# Mcu.net
KiCad netlist of a schematic drawn in Altium Designer
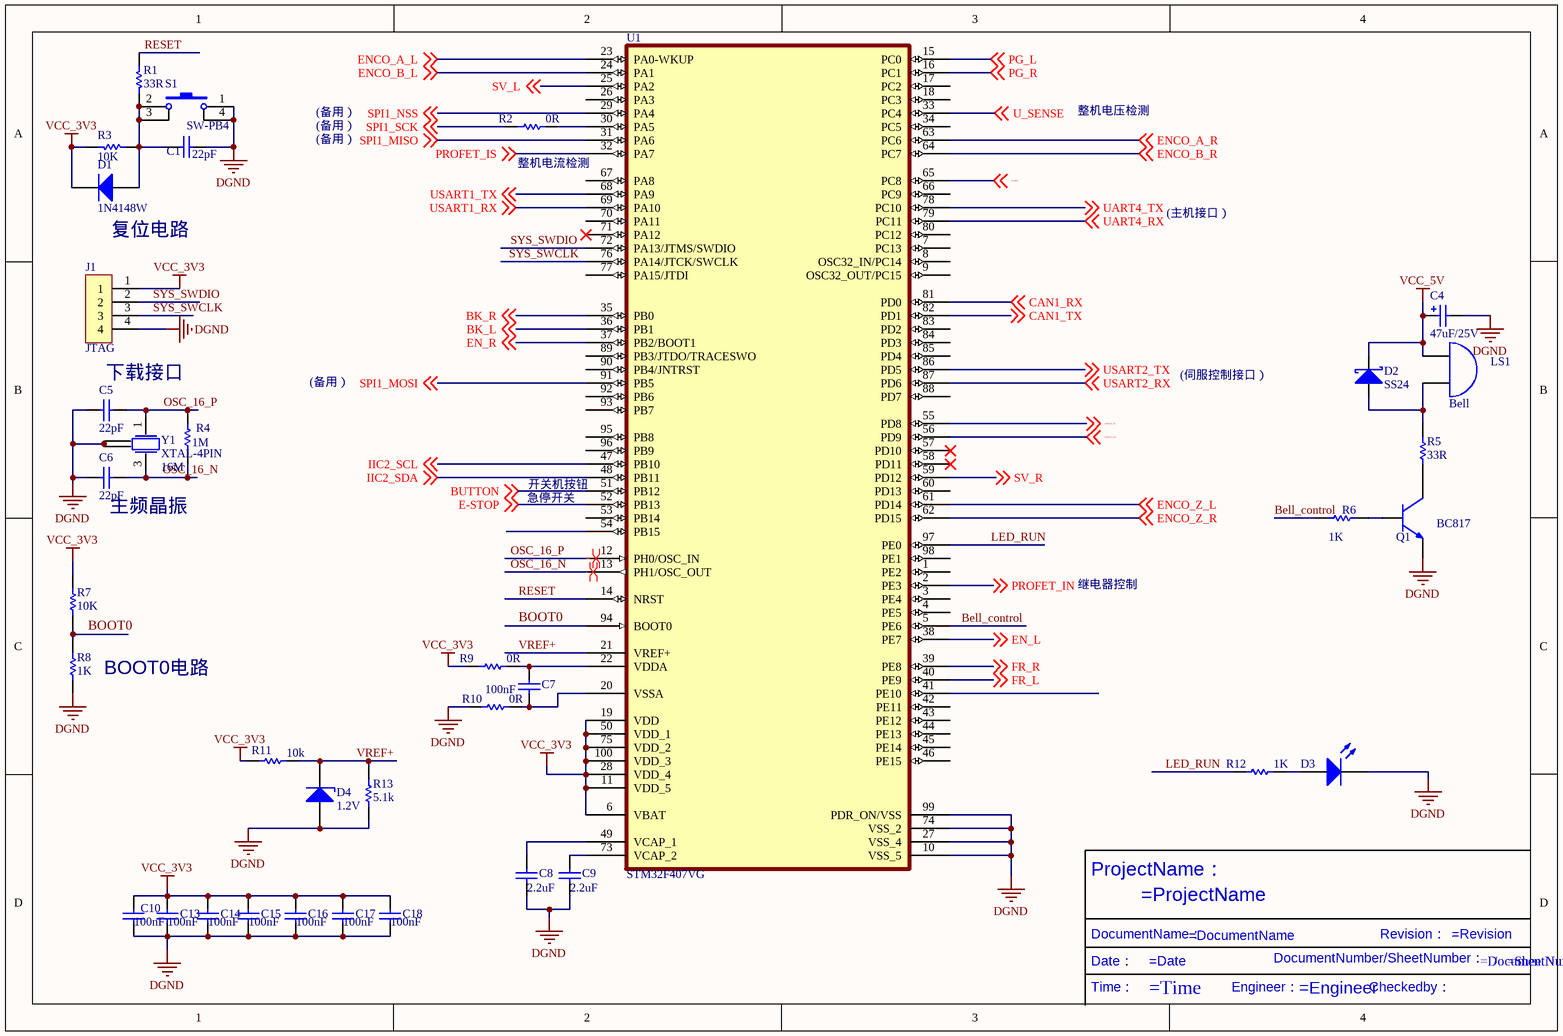
[diagram p0: Mcu.SchDoc]

(export (version "E")
  (design (tool "Eeschema 10.0.6"))
  (components
    (comp (ref "C1")
      (value "22pF")
      (footprint "C0805")
      (description "Capacitor")
      (fields (field (name "Comment") "Cap") (field (name "PUBLISHER") "Altium Limited"))
      (libsource (lib "boocax_schlib") (part "Cap"))
    )
    (comp (ref "C4")
      (value "47uF/25V")
      (footprint "CAP-1206")
      (description "Polarized Capacitor (Radial)")
      (fields (field (name "Comment") "Cap Pol1") (field (name "PUBLISHER") "Altium Limited"))
      (libsource (lib "boocax_schlib") (part "Cap Pol1"))
    )
    (comp (ref "C5")
      (value "22pF")
      (footprint "C0805")
      (description "Capacitor")
      (fields (field (name "Comment") "Cap") (field (name "PUBLISHER") "Altium Limited"))
      (libsource (lib "boocax_schlib") (part "Cap"))
    )
    (comp (ref "C6")
      (value "22pF")
      (footprint "C0805")
      (description "Capacitor")
      (fields (field (name "Comment") "Cap") (field (name "PUBLISHER") "Altium Limited"))
      (libsource (lib "boocax_schlib") (part "Cap"))
    )
    (comp (ref "C7")
      (value "100nF")
      (footprint "C0805")
      (description "Capacitor")
      (fields (field (name "Comment") "Cap") (field (name "PUBLISHER") "Altium Limited"))
      (libsource (lib "boocax_schlib") (part "Cap"))
    )
    (comp (ref "C8")
      (value "2.2uF")
      (footprint "C0805")
      (description "Capacitor")
      (fields (field (name "Comment") "Cap") (field (name "PUBLISHER") "Altium Limited"))
      (libsource (lib "boocax_schlib") (part "Cap"))
    )
    (comp (ref "C9")
      (value "2.2uF")
      (footprint "C0805")
      (description "Capacitor")
      (fields (field (name "Comment") "Cap") (field (name "PUBLISHER") "Altium Limited"))
      (libsource (lib "boocax_schlib") (part "Cap"))
    )
    (comp (ref "C10")
      (value "100nF")
      (footprint "C0805")
      (description "Capacitor")
      (fields (field (name "Comment") "Cap") (field (name "PUBLISHER") "Altium Limited"))
      (libsource (lib "boocax_schlib") (part "Cap"))
    )
    (comp (ref "C13")
      (value "100nF")
      (footprint "C0805")
      (description "Capacitor")
      (fields (field (name "Comment") "Cap") (field (name "PUBLISHER") "Altium Limited"))
      (libsource (lib "boocax_schlib") (part "Cap"))
    )
    (comp (ref "C14")
      (value "100nF")
      (footprint "C0805")
      (description "Capacitor")
      (fields (field (name "Comment") "Cap") (field (name "PUBLISHER") "Altium Limited"))
      (libsource (lib "boocax_schlib") (part "Cap"))
    )
    (comp (ref "C15")
      (value "100nF")
      (footprint "C0805")
      (description "Capacitor")
      (fields (field (name "Comment") "Cap") (field (name "PUBLISHER") "Altium Limited"))
      (libsource (lib "boocax_schlib") (part "Cap"))
    )
    (comp (ref "C16")
      (value "100nF")
      (footprint "C0805")
      (description "Capacitor")
      (fields (field (name "Comment") "Cap") (field (name "PUBLISHER") "Altium Limited"))
      (libsource (lib "boocax_schlib") (part "Cap"))
    )
    (comp (ref "C17")
      (value "100nF")
      (footprint "C0805")
      (description "Capacitor")
      (fields (field (name "Comment") "Cap") (field (name "PUBLISHER") "Altium Limited"))
      (libsource (lib "boocax_schlib") (part "Cap"))
    )
    (comp (ref "C18")
      (value "100nF")
      (footprint "C0805")
      (description "Capacitor")
      (fields (field (name "Comment") "Cap") (field (name "PUBLISHER") "Altium Limited"))
      (libsource (lib "boocax_schlib") (part "Cap"))
    )
    (comp (ref "D1")
      (value "1N4148W")
      (footprint "DIODE-1206")
      (description "二极管")
      (fields (field (name "Comment") "Diode") (field (name "PUBLISHER") "Altium Limited"))
      (libsource (lib "founder") (part "Diode"))
    )
    (comp (ref "D2")
      (value "SS24")
      (footprint "DIODE-SMA")
      (description "肖特基二极管")
      (fields (field (name "Comment") "Diode-Schottky") (field (name "PUBLISHER") "Altium Limited"))
      (libsource (lib "boocax_schlib-20171017-1-dkw") (part "Diode-Schottky"))
    )
    (comp (ref "D3")
      (value "LED0")
      (footprint "LED_0805")
      (description "发光二极管")
      (fields (field (name "PUBLISHER") "Altium Limited"))
      (libsource (lib "founder") (part "LED0"))
    )
    (comp (ref "D4")
      (value "1.2V")
      (footprint "DIODE-1206")
      (description "稳压二极管")
      (fields (field (name "Comment") "Diode-Z") (field (name "PUBLISHER") "Altium Limited"))
      (libsource (lib "Fszhang") (part "Diode-Z"))
    )
    (comp (ref "J1")
      (value "JTAG")
      (footprint "PORT-SIP4-2.54")
      (libsource (lib "boocax_schlib") (part "Conn_1*4_1"))
    )
    (comp (ref "LS1")
      (value "Bell")
      (footprint "PIN2")
      (description "Electrical Bell")
      (fields (field (name "PUBLISHER") "Altium Limited"))
      (libsource (lib "Miscellaneous Devices") (part "Bell"))
    )
    (comp (ref "Q1")
      (value "BC817")
      (footprint "SOT-23_N")
      (description "NPN 45V 功耗 310mW")
      (libsource (lib "Schlib1") (part "mNPN"))
    )
    (comp (ref "R1")
      (value "33R")
      (footprint "R0805")
      (description "Resistor")
      (fields (field (name "Comment") "Res1") (field (name "PUBLISHER") "Altium Limited"))
      (libsource (lib "boocax_schlib") (part "Res1"))
    )
    (comp (ref "R2")
      (value "0R")
      (footprint "R0805")
      (description "Resistor")
      (fields (field (name "Comment") "Res1") (field (name "PUBLISHER") "Altium Limited"))
      (libsource (lib "boocax_schlib") (part "Res1"))
    )
    (comp (ref "R3")
      (value "10K")
      (footprint "R0805")
      (description "Resistor")
      (fields (field (name "Comment") "Res1") (field (name "PUBLISHER") "Altium Limited"))
      (libsource (lib "boocax_schlib") (part "Res1"))
    )
    (comp (ref "R4")
      (value "1M")
      (footprint "R0805")
      (description "Resistor")
      (fields (field (name "Comment") "Res1") (field (name "PUBLISHER") "Altium Limited"))
      (libsource (lib "boocax_schlib") (part "Res1"))
    )
    (comp (ref "R5")
      (value "33R")
      (footprint "R0805")
      (description "Resistor")
      (fields (field (name "Comment") "Res1") (field (name "PUBLISHER") "Altium Limited"))
      (libsource (lib "boocax_schlib") (part "Res1"))
    )
    (comp (ref "R6")
      (value "1K")
      (footprint "R0805")
      (description "Resistor")
      (fields (field (name "Comment") "Res1") (field (name "PUBLISHER") "Altium Limited"))
      (libsource (lib "boocax_schlib") (part "Res1"))
    )
    (comp (ref "R7")
      (value "10K")
      (footprint "R0805")
      (description "Resistor")
      (fields (field (name "Comment") "Res1") (field (name "PUBLISHER") "Altium Limited"))
      (libsource (lib "boocax_schlib") (part "Res1"))
    )
    (comp (ref "R8")
      (value "1K")
      (footprint "R0805")
      (description "Resistor")
      (fields (field (name "Comment") "Res1") (field (name "PUBLISHER") "Altium Limited"))
      (libsource (lib "boocax_schlib") (part "Res1"))
    )
    (comp (ref "R9")
      (value "0R")
      (footprint "R0805")
      (description "Resistor")
      (fields (field (name "Comment") "Res1") (field (name "PUBLISHER") "Altium Limited"))
      (libsource (lib "boocax_schlib") (part "Res1"))
    )
    (comp (ref "R10")
      (value "0R")
      (footprint "R0805")
      (description "Resistor")
      (fields (field (name "Comment") "Res1") (field (name "PUBLISHER") "Altium Limited"))
      (libsource (lib "boocax_schlib") (part "Res1"))
    )
    (comp (ref "R11")
      (value "10k")
      (footprint "R0805")
      (description "Resistor")
      (fields (field (name "Comment") "Res1") (field (name "PUBLISHER") "Altium Limited"))
      (libsource (lib "boocax_schlib") (part "Res1"))
    )
    (comp (ref "R12")
      (value "1K")
      (footprint "R0805")
      (description "Resistor")
      (fields (field (name "Comment") "Res1") (field (name "PUBLISHER") "Altium Limited"))
      (libsource (lib "boocax_schlib") (part "Res1"))
    )
    (comp (ref "R13")
      (value "5.1k")
      (footprint "R0805")
      (description "Resistor")
      (fields (field (name "Comment") "Res1") (field (name "PUBLISHER") "Altium Limited"))
      (libsource (lib "boocax_schlib") (part "Res1"))
    )
    (comp (ref "S1")
      (value "SW-PB4")
      (footprint "RESET-SMD-1O4")
      (description "微动开关")
      (fields (field (name "PUBLISHER") "Altium Limited"))
      (libsource (lib "boocax_schlib") (part "SW-PB4"))
    )
    (comp (ref "U1")
      (value "STM32F407VG")
      (footprint "100T1_N")
      (libsource (lib "boocax_schlib") (part "STM32F407VG"))
    )
    (comp (ref "Y1")
      (value "XTAL-4PIN")
      (footprint "EPSON-16M")
      (fields (field (name "ALTIUM_VALUE") "16M"))
      (libsource (lib "fszhang") (part "XTAL-4PIN"))
    )
  )
  (nets
    (net (code "9") (name "/BOOT0") (class "Default")
      (node (ref "R7") (pin "2") (pinfunction "2_2") (pintype "passive"))
      (node (ref "R8") (pin "2") (pinfunction "2_2") (pintype "passive"))
      (node (ref "U1") (pin "94") (pinfunction "BOOT0_94") (pintype "input"))
    )
    (net (code "10") (name "/Bell_control") (class "Default")
      (node (ref "R6") (pin "2") (pinfunction "2_2") (pintype "passive"))
      (node (ref "U1") (pin "5") (pinfunction "PE6_5") (pintype "bidirectional"))
    )
    (net (code "16") (name "/LED_RUN") (class "Default")
      (node (ref "R12") (pin "2") (pinfunction "2_2") (pintype "passive"))
      (node (ref "U1") (pin "97") (pinfunction "PE0_97") (pintype "bidirectional"))
    )
    (net (code "17") (name "/OSC_16_N") (class "Default")
      (node (ref "C6") (pin "1") (pinfunction "1_1") (pintype "passive"))
      (node (ref "R4") (pin "1") (pinfunction "1_1") (pintype "passive"))
      (node (ref "U1") (pin "13") (pinfunction "PH1/OSC_OUT_13") (pintype "output"))
      (node (ref "Y1") (pin "3") (pinfunction "3_3") (pintype "passive"))
    )
    (net (code "18") (name "/OSC_16_P") (class "Default")
      (node (ref "C5") (pin "2") (pinfunction "2_2") (pintype "passive"))
      (node (ref "R4") (pin "2") (pinfunction "2_2") (pintype "passive"))
      (node (ref "U1") (pin "12") (pinfunction "PH0/OSC_IN_12") (pintype "input"))
      (node (ref "Y1") (pin "1") (pinfunction "1_1") (pintype "passive"))
    )
    (net (code "20") (name "/RESET") (class "Default")
      (node (ref "R1") (pin "1") (pinfunction "1_1") (pintype "passive"))
      (node (ref "U1") (pin "14") (pinfunction "NRST_14") (pintype "bidirectional"))
    )
    (net (code "22") (name "/SYS_SWCLK") (class "Default")
      (node (ref "J1") (pin "3") (pinfunction "3_3") (pintype "passive"))
      (node (ref "U1") (pin "76") (pinfunction "PA14/JTCK/SWCLK_76") (pintype "bidirectional"))
    )
    (net (code "23") (name "/SYS_SWDIO") (class "Default")
      (node (ref "J1") (pin "2") (pinfunction "2_2") (pintype "passive"))
      (node (ref "U1") (pin "72") (pinfunction "PA13/JTMS/SWDIO_72") (pintype "bidirectional"))
    )
    (net (code "25") (name "/VREF+") (class "Default")
      (node (ref "D4") (pin "2") (pinfunction "K_2") (pintype "passive"))
      (node (ref "R11") (pin "1") (pinfunction "1_1") (pintype "passive"))
      (node (ref "R13") (pin "2") (pinfunction "2_2") (pintype "passive"))
      (node (ref "U1") (pin "21") (pinfunction "VREF+_21") (pintype "power_in"))
    )
    (net (code "27") (name "B-STOP") (class "Default")
      (node (ref "U1") (pin "65") (pinfunction "PC8_65") (pintype "bidirectional"))
    )
    (net (code "28") (name "BK_L") (class "Default")
      (node (ref "U1") (pin "36") (pinfunction "PB1_36") (pintype "bidirectional"))
    )
    (net (code "29") (name "BK_R") (class "Default")
      (node (ref "U1") (pin "35") (pinfunction "PB0_35") (pintype "bidirectional"))
    )
    (net (code "30") (name "BUTTON") (class "Default")
      (node (ref "U1") (pin "51") (pinfunction "PB12_51") (pintype "bidirectional"))
    )
    (net (code "31") (name "CAN1_RX") (class "Default")
      (node (ref "U1") (pin "81") (pinfunction "PD0_81") (pintype "bidirectional"))
    )
    (net (code "32") (name "CAN1_TX") (class "Default")
      (node (ref "U1") (pin "82") (pinfunction "PD1_82") (pintype "bidirectional"))
    )
    (net (code "33") (name "DGND") (class "Default")
      (node (ref "C1") (pin "1") (pinfunction "1_1") (pintype "passive"))
      (node (ref "C10") (pin "2") (pinfunction "2_2") (pintype "passive"))
      (node (ref "C13") (pin "2") (pinfunction "2_2") (pintype "passive"))
      (node (ref "C14") (pin "2") (pinfunction "2_2") (pintype "passive"))
      (node (ref "C15") (pin "2") (pinfunction "2_2") (pintype "passive"))
      (node (ref "C16") (pin "2") (pinfunction "2_2") (pintype "passive"))
      (node (ref "C17") (pin "2") (pinfunction "2_2") (pintype "passive"))
      (node (ref "C18") (pin "2") (pinfunction "2_2") (pintype "passive"))
      (node (ref "C4") (pin "2") (pinfunction "2_2") (pintype "passive"))
      (node (ref "C5") (pin "1") (pinfunction "1_1") (pintype "passive"))
      (node (ref "C6") (pin "2") (pinfunction "2_2") (pintype "passive"))
      (node (ref "C8") (pin "2") (pinfunction "2_2") (pintype "passive"))
      (node (ref "C9") (pin "2") (pinfunction "2_2") (pintype "passive"))
      (node (ref "D3") (pin "2") (pinfunction "K_2") (pintype "passive"))
      (node (ref "D4") (pin "1") (pinfunction "A_1") (pintype "passive"))
      (node (ref "J1") (pin "4") (pinfunction "4_4") (pintype "passive"))
      (node (ref "Q1") (pin "2") (pinfunction "E_2") (pintype "passive"))
      (node (ref "R10") (pin "2") (pinfunction "2_2") (pintype "passive"))
      (node (ref "R13") (pin "1") (pinfunction "1_1") (pintype "passive"))
      (node (ref "R8") (pin "1") (pinfunction "1_1") (pintype "passive"))
      (node (ref "S1") (pin "1") (pinfunction "1_1") (pintype "passive"))
      (node (ref "S1") (pin "4") (pinfunction "4_4") (pintype "passive"))
      (node (ref "U1") (pin "10") (pinfunction "VSS_5_10") (pintype "passive"))
      (node (ref "U1") (pin "27") (pinfunction "VSS_4_27") (pintype "passive"))
      (node (ref "U1") (pin "74") (pinfunction "VSS_2_74") (pintype "passive"))
      (node (ref "U1") (pin "99") (pinfunction "PDR_ON/VSS_99") (pintype "power_in"))
      (node (ref "Y1") (pin "2") (pinfunction "2_2") (pintype "passive"))
      (node (ref "Y1") (pin "4") (pinfunction "4_4") (pintype "passive"))
    )
    (net (code "34") (name "E-STOP") (class "Default")
      (node (ref "U1") (pin "52") (pinfunction "PB13_52") (pintype "bidirectional"))
    )
    (net (code "35") (name "ENCO_A_L") (class "Default")
      (node (ref "U1") (pin "23") (pinfunction "PA0-WKUP_23") (pintype "bidirectional"))
    )
    (net (code "36") (name "ENCO_A_R") (class "Default")
      (node (ref "U1") (pin "63") (pinfunction "PC6_63") (pintype "bidirectional"))
    )
    (net (code "37") (name "ENCO_B_L") (class "Default")
      (node (ref "U1") (pin "24") (pinfunction "PA1_24") (pintype "bidirectional"))
    )
    (net (code "38") (name "ENCO_B_R") (class "Default")
      (node (ref "U1") (pin "64") (pinfunction "PC7_64") (pintype "bidirectional"))
    )
    (net (code "39") (name "ENCO_Z_L") (class "Default")
      (node (ref "U1") (pin "61") (pinfunction "PD14_61") (pintype "bidirectional"))
    )
    (net (code "40") (name "ENCO_Z_R") (class "Default")
      (node (ref "U1") (pin "62") (pinfunction "PD15_62") (pintype "bidirectional"))
    )
    (net (code "41") (name "EN_L") (class "Default")
      (node (ref "U1") (pin "38") (pinfunction "PE7_38") (pintype "bidirectional"))
    )
    (net (code "42") (name "EN_R") (class "Default")
      (node (ref "U1") (pin "37") (pinfunction "PB2/BOOT1_37") (pintype "bidirectional"))
    )
    (net (code "43") (name "FR_L") (class "Default")
      (node (ref "U1") (pin "40") (pinfunction "PE9_40") (pintype "bidirectional"))
    )
    (net (code "44") (name "FR_R") (class "Default")
      (node (ref "U1") (pin "39") (pinfunction "PE8_39") (pintype "bidirectional"))
    )
    (net (code "45") (name "IIC2_SCL") (class "Default")
      (node (ref "U1") (pin "47") (pinfunction "PB10_47") (pintype "bidirectional"))
    )
    (net (code "46") (name "IIC2_SDA") (class "Default")
      (node (ref "U1") (pin "48") (pinfunction "PB11_48") (pintype "bidirectional"))
    )
    (net (code "47") (name "Net-(D1-A)") (class "Default")
      (node (ref "C1") (pin "2") (pinfunction "2_2") (pintype "passive"))
      (node (ref "D1") (pin "1") (pinfunction "A_1") (pintype "passive"))
      (node (ref "R1") (pin "2") (pinfunction "2_2") (pintype "passive"))
      (node (ref "R3") (pin "1") (pinfunction "1_1") (pintype "passive"))
      (node (ref "S1") (pin "2") (pinfunction "2_2") (pintype "passive"))
      (node (ref "S1") (pin "3") (pinfunction "3_3") (pintype "passive"))
    )
    (net (code "48") (name "Net-(D2-A)") (class "Default")
      (node (ref "D2") (pin "1") (pinfunction "A_1") (pintype "passive"))
      (node (ref "LS1") (pin "2") (pinfunction "B_2") (pintype "passive"))
      (node (ref "R5") (pin "1") (pinfunction "1_1") (pintype "passive"))
    )
    (net (code "49") (name "Net-(D3-A)") (class "Default")
      (node (ref "D3") (pin "1") (pinfunction "A_1") (pintype "passive"))
      (node (ref "R12") (pin "1") (pinfunction "1_1") (pintype "passive"))
    )
    (net (code "50") (name "Net-(Q1-B)") (class "Default")
      (node (ref "Q1") (pin "1") (pinfunction "B_1") (pintype "passive"))
      (node (ref "R6") (pin "1") (pinfunction "1_1") (pintype "passive"))
    )
    (net (code "51") (name "Net-(Q1-C)") (class "Default")
      (node (ref "Q1") (pin "3") (pinfunction "C_3") (pintype "passive"))
      (node (ref "R5") (pin "2") (pinfunction "2_2") (pintype "passive"))
    )
    (net (code "52") (name "Net-(U1-PA5)") (class "Default")
      (node (ref "R2") (pin "1") (pinfunction "1_1") (pintype "passive"))
      (node (ref "U1") (pin "30") (pinfunction "PA5_30") (pintype "bidirectional"))
    )
    (net (code "53") (name "Net-(U1-VCAP_1)") (class "Default")
      (node (ref "C8") (pin "1") (pinfunction "1_1") (pintype "passive"))
      (node (ref "U1") (pin "49") (pinfunction "VCAP_1_49") (pintype "power_in"))
    )
    (net (code "54") (name "Net-(U1-VCAP_2)") (class "Default")
      (node (ref "C9") (pin "1") (pinfunction "1_1") (pintype "passive"))
      (node (ref "U1") (pin "73") (pinfunction "VCAP_2_73") (pintype "power_in"))
    )
    (net (code "55") (name "Net-(U1-VDDA)") (class "Default")
      (node (ref "C7") (pin "2") (pinfunction "2_2") (pintype "passive"))
      (node (ref "R9") (pin "1") (pinfunction "1_1") (pintype "passive"))
      (node (ref "U1") (pin "22") (pinfunction "VDDA_22") (pintype "power_in"))
    )
    (net (code "56") (name "Net-(U1-VSSA)") (class "Default")
      (node (ref "C7") (pin "1") (pinfunction "1_1") (pintype "passive"))
      (node (ref "R10") (pin "1") (pinfunction "1_1") (pintype "passive"))
      (node (ref "U1") (pin "20") (pinfunction "VSSA_20") (pintype "power_in"))
    )
    (net (code "57") (name "PG_L") (class "Default")
      (node (ref "U1") (pin "15") (pinfunction "PC0_15") (pintype "bidirectional"))
    )
    (net (code "58") (name "PG_R") (class "Default")
      (node (ref "U1") (pin "16") (pinfunction "PC1_16") (pintype "bidirectional"))
    )
    (net (code "59") (name "PROFET_IN") (class "Default")
      (node (ref "U1") (pin "2") (pinfunction "PE3_2") (pintype "bidirectional"))
    )
    (net (code "60") (name "PROFET_IS") (class "Default")
      (node (ref "U1") (pin "32") (pinfunction "PA7_32") (pintype "bidirectional"))
    )
    (net (code "61") (name "SPI1_MISO") (class "Default")
      (node (ref "U1") (pin "31") (pinfunction "PA6_31") (pintype "bidirectional"))
    )
    (net (code "62") (name "SPI1_MOSI") (class "Default")
      (node (ref "U1") (pin "91") (pinfunction "PB5_91") (pintype "bidirectional"))
    )
    (net (code "63") (name "SPI1_NSS") (class "Default")
      (node (ref "U1") (pin "29") (pinfunction "PA4_29") (pintype "bidirectional"))
    )
    (net (code "64") (name "SPI1_SCK") (class "Default")
      (node (ref "R2") (pin "2") (pinfunction "2_2") (pintype "passive"))
    )
    (net (code "65") (name "SV_L") (class "Default")
      (node (ref "U1") (pin "25") (pinfunction "PA2_25") (pintype "bidirectional"))
    )
    (net (code "66") (name "SV_R") (class "Default")
      (node (ref "U1") (pin "59") (pinfunction "PD12_59") (pintype "bidirectional"))
    )
    (net (code "67") (name "UART4_RX") (class "Default")
      (node (ref "U1") (pin "79") (pinfunction "PC11_79") (pintype "bidirectional"))
    )
    (net (code "68") (name "UART4_TX") (class "Default")
      (node (ref "U1") (pin "78") (pinfunction "PC10_78") (pintype "bidirectional"))
    )
    (net (code "69") (name "USART1_RX") (class "Default")
      (node (ref "U1") (pin "69") (pinfunction "PA10_69") (pintype "bidirectional"))
    )
    (net (code "70") (name "USART1_TX") (class "Default")
      (node (ref "U1") (pin "68") (pinfunction "PA9_68") (pintype "bidirectional"))
    )
    (net (code "71") (name "USART2_RX") (class "Default")
      (node (ref "U1") (pin "87") (pinfunction "PD6_87") (pintype "bidirectional"))
    )
    (net (code "72") (name "USART2_TX") (class "Default")
      (node (ref "U1") (pin "86") (pinfunction "PD5_86") (pintype "bidirectional"))
    )
    (net (code "73") (name "USART3_RX") (class "Default")
      (node (ref "U1") (pin "56") (pinfunction "PD9_56") (pintype "bidirectional"))
    )
    (net (code "74") (name "USART3_TX") (class "Default")
      (node (ref "U1") (pin "55") (pinfunction "PD8_55") (pintype "bidirectional"))
    )
    (net (code "75") (name "U_SENSE") (class "Default")
      (node (ref "U1") (pin "33") (pinfunction "PC4_33") (pintype "bidirectional"))
    )
    (net (code "76") (name "VCC_3V3") (class "Default")
      (node (ref "C10") (pin "1") (pinfunction "1_1") (pintype "passive"))
      (node (ref "C13") (pin "1") (pinfunction "1_1") (pintype "passive"))
      (node (ref "C14") (pin "1") (pinfunction "1_1") (pintype "passive"))
      (node (ref "C15") (pin "1") (pinfunction "1_1") (pintype "passive"))
      (node (ref "C16") (pin "1") (pinfunction "1_1") (pintype "passive"))
      (node (ref "C17") (pin "1") (pinfunction "1_1") (pintype "passive"))
      (node (ref "C18") (pin "1") (pinfunction "1_1") (pintype "passive"))
      (node (ref "D1") (pin "2") (pinfunction "K_2") (pintype "passive"))
      (node (ref "J1") (pin "1") (pinfunction "1_1") (pintype "passive"))
      (node (ref "R11") (pin "2") (pinfunction "2_2") (pintype "passive"))
      (node (ref "R3") (pin "2") (pinfunction "2_2") (pintype "passive"))
      (node (ref "R7") (pin "1") (pinfunction "1_1") (pintype "passive"))
      (node (ref "R9") (pin "2") (pinfunction "2_2") (pintype "passive"))
      (node (ref "U1") (pin "100") (pinfunction "VDD_3_100") (pintype "power_in"))
      (node (ref "U1") (pin "11") (pinfunction "VDD_5_11") (pintype "power_in"))
      (node (ref "U1") (pin "19") (pinfunction "VDD_19") (pintype "power_in"))
      (node (ref "U1") (pin "28") (pinfunction "VDD_4_28") (pintype "power_in"))
      (node (ref "U1") (pin "50") (pinfunction "VDD_1_50") (pintype "power_in"))
      (node (ref "U1") (pin "6") (pinfunction "VBAT_6") (pintype "power_in"))
      (node (ref "U1") (pin "75") (pinfunction "VDD_2_75") (pintype "power_in"))
    )
    (net (code "77") (name "VCC_5V") (class "Default")
      (node (ref "C4") (pin "1") (pinfunction "1_1") (pintype "passive"))
      (node (ref "D2") (pin "2") (pinfunction "K_2") (pintype "passive"))
      (node (ref "LS1") (pin "1") (pinfunction "A_1") (pintype "passive"))
    )
    (net (code "78") (name "unconnected-(U1-OSC32_IN{slash}PC14-Pad8)") (class "Default")
      (node (ref "U1") (pin "8") (pinfunction "OSC32_IN/PC14_8") (pintype "bidirectional"))
    )
    (net (code "79") (name "unconnected-(U1-OSC32_OUT{slash}PC15-Pad9)") (class "Default")
      (node (ref "U1") (pin "9") (pinfunction "OSC32_OUT/PC15_9") (pintype "bidirectional"))
    )
    (net (code "80") (name "unconnected-(U1-PA3-Pad26)") (class "Default")
      (node (ref "U1") (pin "26") (pinfunction "PA3_26") (pintype "bidirectional"))
    )
    (net (code "81") (name "unconnected-(U1-PA8-Pad67)") (class "Default")
      (node (ref "U1") (pin "67") (pinfunction "PA8_67") (pintype "bidirectional"))
    )
    (net (code "82") (name "unconnected-(U1-PA11-Pad70)") (class "Default")
      (node (ref "U1") (pin "70") (pinfunction "PA11_70") (pintype "bidirectional"))
    )
    (net (code "83") (name "unconnected-(U1-PA12-Pad71)") (class "Default")
      (node (ref "U1") (pin "71") (pinfunction "PA12_71") (pintype "bidirectional+no_connect"))
    )
    (net (code "84") (name "unconnected-(U1-PA15{slash}JTDI-Pad77)") (class "Default")
      (node (ref "U1") (pin "77") (pinfunction "PA15/JTDI_77") (pintype "bidirectional"))
    )
    (net (code "85") (name "unconnected-(U1-PB3{slash}JTDO{slash}TRACESWO-Pad89)") (class "Default")
      (node (ref "U1") (pin "89") (pinfunction "PB3/JTDO/TRACESWO_89") (pintype "bidirectional"))
    )
    (net (code "86") (name "unconnected-(U1-PB4{slash}JNTRST-Pad90)") (class "Default")
      (node (ref "U1") (pin "90") (pinfunction "PB4/JNTRST_90") (pintype "bidirectional"))
    )
    (net (code "87") (name "unconnected-(U1-PB6-Pad92)") (class "Default")
      (node (ref "U1") (pin "92") (pinfunction "PB6_92") (pintype "bidirectional"))
    )
    (net (code "88") (name "unconnected-(U1-PB7-Pad93)") (class "Default")
      (node (ref "U1") (pin "93") (pinfunction "PB7_93") (pintype "bidirectional"))
    )
    (net (code "89") (name "unconnected-(U1-PB8-Pad95)") (class "Default")
      (node (ref "U1") (pin "95") (pinfunction "PB8_95") (pintype "bidirectional"))
    )
    (net (code "90") (name "unconnected-(U1-PB9-Pad96)") (class "Default")
      (node (ref "U1") (pin "96") (pinfunction "PB9_96") (pintype "bidirectional"))
    )
    (net (code "91") (name "unconnected-(U1-PB14-Pad53)") (class "Default")
      (node (ref "U1") (pin "53") (pinfunction "PB14_53") (pintype "bidirectional"))
    )
    (net (code "92") (name "unconnected-(U1-PB15-Pad54)") (class "Default")
      (node (ref "U1") (pin "54") (pinfunction "PB15_54") (pintype "bidirectional"))
    )
    (net (code "93") (name "unconnected-(U1-PC2-Pad17)") (class "Default")
      (node (ref "U1") (pin "17") (pinfunction "PC2_17") (pintype "bidirectional"))
    )
    (net (code "94") (name "unconnected-(U1-PC3-Pad18)") (class "Default")
      (node (ref "U1") (pin "18") (pinfunction "PC3_18") (pintype "bidirectional"))
    )
    (net (code "95") (name "unconnected-(U1-PC5-Pad34)") (class "Default")
      (node (ref "U1") (pin "34") (pinfunction "PC5_34") (pintype "bidirectional"))
    )
    (net (code "96") (name "unconnected-(U1-PC9-Pad66)") (class "Default")
      (node (ref "U1") (pin "66") (pinfunction "PC9_66") (pintype "bidirectional"))
    )
    (net (code "97") (name "unconnected-(U1-PC12-Pad80)") (class "Default")
      (node (ref "U1") (pin "80") (pinfunction "PC12_80") (pintype "bidirectional"))
    )
    (net (code "98") (name "unconnected-(U1-PC13-Pad7)") (class "Default")
      (node (ref "U1") (pin "7") (pinfunction "PC13_7") (pintype "bidirectional"))
    )
    (net (code "99") (name "unconnected-(U1-PD2-Pad83)") (class "Default")
      (node (ref "U1") (pin "83") (pinfunction "PD2_83") (pintype "bidirectional"))
    )
    (net (code "100") (name "unconnected-(U1-PD3-Pad84)") (class "Default")
      (node (ref "U1") (pin "84") (pinfunction "PD3_84") (pintype "bidirectional"))
    )
    (net (code "101") (name "unconnected-(U1-PD4-Pad85)") (class "Default")
      (node (ref "U1") (pin "85") (pinfunction "PD4_85") (pintype "bidirectional"))
    )
    (net (code "102") (name "unconnected-(U1-PD7-Pad88)") (class "Default")
      (node (ref "U1") (pin "88") (pinfunction "PD7_88") (pintype "bidirectional"))
    )
    (net (code "103") (name "unconnected-(U1-PD10-Pad57)") (class "Default")
      (node (ref "U1") (pin "57") (pinfunction "PD10_57") (pintype "bidirectional+no_connect"))
    )
    (net (code "104") (name "unconnected-(U1-PD11-Pad58)") (class "Default")
      (node (ref "U1") (pin "58") (pinfunction "PD11_58") (pintype "bidirectional+no_connect"))
    )
    (net (code "105") (name "unconnected-(U1-PD13-Pad60)") (class "Default")
      (node (ref "U1") (pin "60") (pinfunction "PD13_60") (pintype "bidirectional"))
    )
    (net (code "106") (name "unconnected-(U1-PE1-Pad98)") (class "Default")
      (node (ref "U1") (pin "98") (pinfunction "PE1_98") (pintype "bidirectional"))
    )
    (net (code "107") (name "unconnected-(U1-PE2-Pad1)") (class "Default")
      (node (ref "U1") (pin "1") (pinfunction "PE2_1") (pintype "bidirectional"))
    )
    (net (code "108") (name "unconnected-(U1-PE4-Pad3)") (class "Default")
      (node (ref "U1") (pin "3") (pinfunction "PE4_3") (pintype "bidirectional"))
    )
    (net (code "109") (name "unconnected-(U1-PE5-Pad4)") (class "Default")
      (node (ref "U1") (pin "4") (pinfunction "PE5_4") (pintype "bidirectional"))
    )
    (net (code "110") (name "unconnected-(U1-PE10-Pad41)") (class "Default")
      (node (ref "U1") (pin "41") (pinfunction "PE10_41") (pintype "bidirectional"))
    )
    (net (code "111") (name "unconnected-(U1-PE11-Pad42)") (class "Default")
      (node (ref "U1") (pin "42") (pinfunction "PE11_42") (pintype "bidirectional"))
    )
    (net (code "112") (name "unconnected-(U1-PE12-Pad43)") (class "Default")
      (node (ref "U1") (pin "43") (pinfunction "PE12_43") (pintype "bidirectional"))
    )
    (net (code "113") (name "unconnected-(U1-PE13-Pad44)") (class "Default")
      (node (ref "U1") (pin "44") (pinfunction "PE13_44") (pintype "bidirectional"))
    )
    (net (code "114") (name "unconnected-(U1-PE14-Pad45)") (class "Default")
      (node (ref "U1") (pin "45") (pinfunction "PE14_45") (pintype "bidirectional"))
    )
    (net (code "115") (name "unconnected-(U1-PE15-Pad46)") (class "Default")
      (node (ref "U1") (pin "46") (pinfunction "PE15_46") (pintype "bidirectional"))
    )
  )
)
